# BB-OR-NAND_v1_1.net
KiCad netlist of a schematic drawn in EAGLE
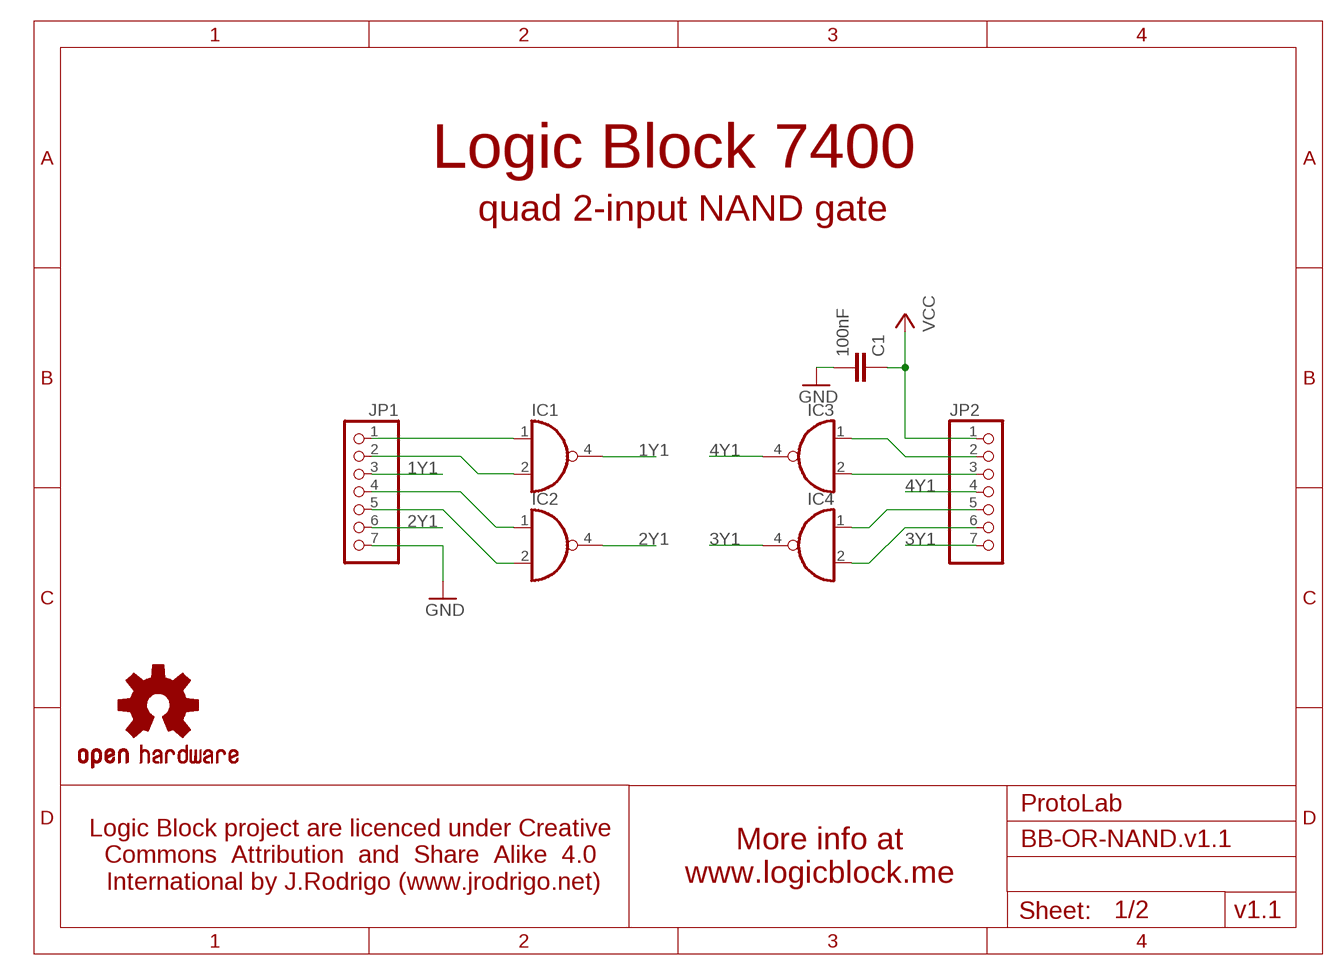
[diagram p0: schematic, sheet 1]
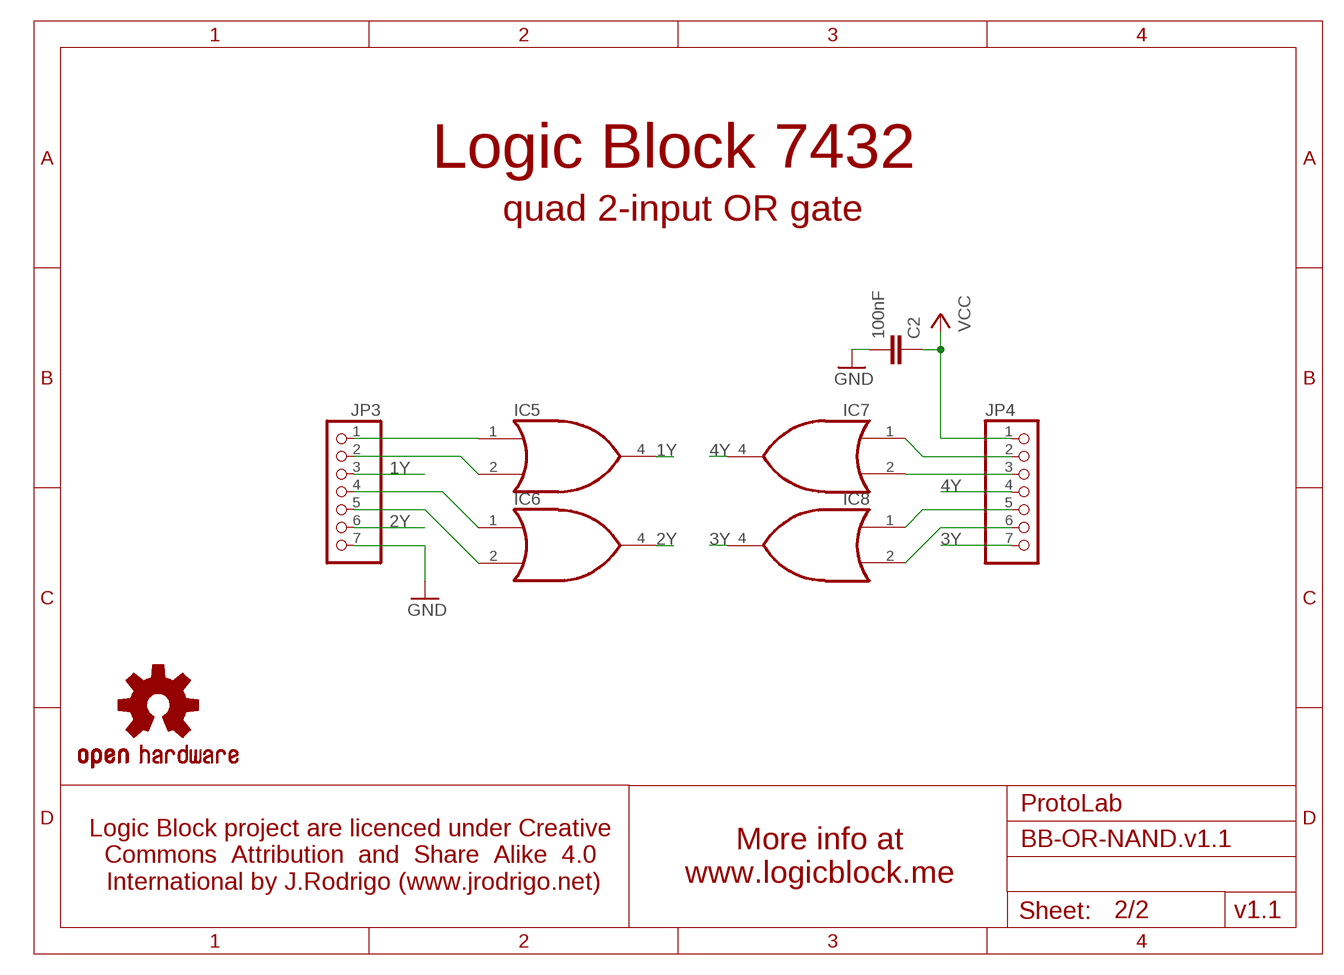
[diagram p1: schematic, sheet 2]

(export (version "E")
  (design (tool "Eeschema 10.0.6"))
  (components
    (comp (ref "C2")
      (value "100nF")
      (footprint "eagle-import:C0603K")
      (libsource (lib "eagle-import") (part "C-EUC0603K"))
    )
    (comp (ref "IC5")
      (value "74AHC1G32DCK")
      (footprint "eagle-import:SC70-5")
      (libsource (lib "eagle-import") (part "741G32DCKAHC"))
    )
    (comp (ref "IC6")
      (value "74AHC1G32DCK")
      (footprint "eagle-import:SC70-5")
      (libsource (lib "eagle-import") (part "741G32DCKAHC"))
    )
    (comp (ref "IC7")
      (value "74AHC1G32DCK")
      (footprint "eagle-import:SC70-5")
      (libsource (lib "eagle-import") (part "741G32DCKAHC"))
    )
    (comp (ref "IC8")
      (value "74AHC1G32DCK")
      (footprint "eagle-import:SC70-5")
      (libsource (lib "eagle-import") (part "741G32DCKAHC"))
    )
    (comp (ref "JP3")
      (value "CON_1X7CLEANBIG")
      (footprint "eagle-import:CON_1X07-CLEANBIG")
      (libsource (lib "eagle-import") (part "CON_1X7CLEANBIG"))
    )
    (comp (ref "JP4")
      (value "CON_1X7CLEANBIG")
      (footprint "eagle-import:CON_1X07-CLEANBIG")
      (libsource (lib "eagle-import") (part "CON_1X7CLEANBIG"))
    )
    (comp (ref "U$2")
      (value "OSHW-LOGOS-LAYER230")
      (footprint "eagle-import:OSHW-LOGO-S_LAYER230")
      (libsource (lib "eagle-import") (part "OSHW-LOGOS-LAYER230"))
    )
    (comp (ref "C1")
      (value "100nF")
      (footprint "eagle-import:C0603K")
      (libsource (lib "eagle-import") (part "C-EUC0603K"))
    )
    (comp (ref "IC1")
      (value "74AHC1G00DCK")
      (footprint "eagle-import:SC70-5")
      (libsource (lib "eagle-import") (part "741G00DCKAHC"))
    )
    (comp (ref "IC2")
      (value "74AHC1G00DCK")
      (footprint "eagle-import:SC70-5")
      (libsource (lib "eagle-import") (part "741G00DCKAHC"))
    )
    (comp (ref "IC3")
      (value "74AHC1G00DCK")
      (footprint "eagle-import:SC70-5")
      (libsource (lib "eagle-import") (part "741G00DCKAHC"))
    )
    (comp (ref "IC4")
      (value "74AHC1G00DCK")
      (footprint "eagle-import:SC70-5")
      (libsource (lib "eagle-import") (part "741G00DCKAHC"))
    )
    (comp (ref "JP1")
      (value "CON_1X7CLEANBIG")
      (footprint "eagle-import:CON_1X07-CLEANBIG")
      (libsource (lib "eagle-import") (part "CON_1X7CLEANBIG"))
    )
    (comp (ref "JP2")
      (value "CON_1X7CLEANBIG")
      (footprint "eagle-import:CON_1X07-CLEANBIG")
      (libsource (lib "eagle-import") (part "CON_1X7CLEANBIG"))
    )
    (comp (ref "U$1")
      (value "OSHW-LOGOS-LAYER230")
      (footprint "eagle-import:OSHW-LOGO-S_LAYER230")
      (libsource (lib "eagle-import") (part "OSHW-LOGOS-LAYER230"))
    )
  )
  (nets
    (net (code "1") (name "1Y") (class "Default")
      (node (ref "IC5") (pin "4") (pinfunction "O_4") (pintype "output"))
      (node (ref "JP3") (pin "3") (pinfunction "3_3") (pintype "passive"))
    )
    (net (code "2") (name "1Y1") (class "Default")
      (node (ref "IC1") (pin "4") (pinfunction "O_4") (pintype "output"))
      (node (ref "JP1") (pin "3") (pinfunction "3_3") (pintype "passive"))
    )
    (net (code "3") (name "2Y") (class "Default")
      (node (ref "IC6") (pin "4") (pinfunction "O_4") (pintype "output"))
      (node (ref "JP3") (pin "6") (pinfunction "6_6") (pintype "passive"))
    )
    (net (code "4") (name "2Y1") (class "Default")
      (node (ref "IC2") (pin "4") (pinfunction "O_4") (pintype "output"))
      (node (ref "JP1") (pin "6") (pinfunction "6_6") (pintype "passive"))
    )
    (net (code "5") (name "3Y") (class "Default")
      (node (ref "IC8") (pin "4") (pinfunction "O_4") (pintype "output"))
      (node (ref "JP4") (pin "7") (pinfunction "7_7") (pintype "passive"))
    )
    (net (code "6") (name "3Y1") (class "Default")
      (node (ref "IC4") (pin "4") (pinfunction "O_4") (pintype "output"))
      (node (ref "JP2") (pin "7") (pinfunction "7_7") (pintype "passive"))
    )
    (net (code "7") (name "4Y") (class "Default")
      (node (ref "IC7") (pin "4") (pinfunction "O_4") (pintype "output"))
      (node (ref "JP4") (pin "4") (pinfunction "4_4") (pintype "passive"))
    )
    (net (code "8") (name "4Y1") (class "Default")
      (node (ref "IC3") (pin "4") (pinfunction "O_4") (pintype "output"))
      (node (ref "JP2") (pin "4") (pinfunction "4_4") (pintype "passive"))
    )
    (net (code "9") (name "GND") (class "Default")
      (node (ref "C1") (pin "2") (pinfunction "2_2") (pintype "passive"))
      (node (ref "C2") (pin "2") (pinfunction "2_2") (pintype "passive"))
      (node (ref "JP1") (pin "7") (pinfunction "7_7") (pintype "passive"))
      (node (ref "JP3") (pin "7") (pinfunction "7_7") (pintype "passive"))
    )
    (net (code "10") (name "Net-(IC1A-I0)") (class "Default")
      (node (ref "IC1") (pin "1") (pinfunction "I0_1") (pintype "input"))
      (node (ref "JP1") (pin "1") (pinfunction "1_1") (pintype "passive"))
    )
    (net (code "11") (name "Net-(IC1A-I1)") (class "Default")
      (node (ref "IC1") (pin "2") (pinfunction "I1_2") (pintype "input"))
      (node (ref "JP1") (pin "2") (pinfunction "2_2") (pintype "passive"))
    )
    (net (code "12") (name "Net-(IC2A-I0)") (class "Default")
      (node (ref "IC2") (pin "1") (pinfunction "I0_1") (pintype "input"))
      (node (ref "JP1") (pin "4") (pinfunction "4_4") (pintype "passive"))
    )
    (net (code "13") (name "Net-(IC2A-I1)") (class "Default")
      (node (ref "IC2") (pin "2") (pinfunction "I1_2") (pintype "input"))
      (node (ref "JP1") (pin "5") (pinfunction "5_5") (pintype "passive"))
    )
    (net (code "14") (name "Net-(IC3A-I0)") (class "Default")
      (node (ref "IC3") (pin "1") (pinfunction "I0_1") (pintype "input"))
      (node (ref "JP2") (pin "2") (pinfunction "2_2") (pintype "passive"))
    )
    (net (code "15") (name "Net-(IC3A-I1)") (class "Default")
      (node (ref "IC3") (pin "2") (pinfunction "I1_2") (pintype "input"))
      (node (ref "JP2") (pin "3") (pinfunction "3_3") (pintype "passive"))
    )
    (net (code "16") (name "Net-(IC4A-I0)") (class "Default")
      (node (ref "IC4") (pin "1") (pinfunction "I0_1") (pintype "input"))
      (node (ref "JP2") (pin "5") (pinfunction "5_5") (pintype "passive"))
    )
    (net (code "17") (name "Net-(IC4A-I1)") (class "Default")
      (node (ref "IC4") (pin "2") (pinfunction "I1_2") (pintype "input"))
      (node (ref "JP2") (pin "6") (pinfunction "6_6") (pintype "passive"))
    )
    (net (code "18") (name "Net-(IC5A-I0)") (class "Default")
      (node (ref "IC5") (pin "1") (pinfunction "I0_1") (pintype "input"))
      (node (ref "JP3") (pin "1") (pinfunction "1_1") (pintype "passive"))
    )
    (net (code "19") (name "Net-(IC5A-I1)") (class "Default")
      (node (ref "IC5") (pin "2") (pinfunction "I1_2") (pintype "input"))
      (node (ref "JP3") (pin "2") (pinfunction "2_2") (pintype "passive"))
    )
    (net (code "20") (name "Net-(IC6A-I0)") (class "Default")
      (node (ref "IC6") (pin "1") (pinfunction "I0_1") (pintype "input"))
      (node (ref "JP3") (pin "4") (pinfunction "4_4") (pintype "passive"))
    )
    (net (code "21") (name "Net-(IC6A-I1)") (class "Default")
      (node (ref "IC6") (pin "2") (pinfunction "I1_2") (pintype "input"))
      (node (ref "JP3") (pin "5") (pinfunction "5_5") (pintype "passive"))
    )
    (net (code "22") (name "Net-(IC7A-I0)") (class "Default")
      (node (ref "IC7") (pin "1") (pinfunction "I0_1") (pintype "input"))
      (node (ref "JP4") (pin "2") (pinfunction "2_2") (pintype "passive"))
    )
    (net (code "23") (name "Net-(IC7A-I1)") (class "Default")
      (node (ref "IC7") (pin "2") (pinfunction "I1_2") (pintype "input"))
      (node (ref "JP4") (pin "3") (pinfunction "3_3") (pintype "passive"))
    )
    (net (code "24") (name "Net-(IC8A-I0)") (class "Default")
      (node (ref "IC8") (pin "1") (pinfunction "I0_1") (pintype "input"))
      (node (ref "JP4") (pin "5") (pinfunction "5_5") (pintype "passive"))
    )
    (net (code "25") (name "Net-(IC8A-I1)") (class "Default")
      (node (ref "IC8") (pin "2") (pinfunction "I1_2") (pintype "input"))
      (node (ref "JP4") (pin "6") (pinfunction "6_6") (pintype "passive"))
    )
    (net (code "26") (name "VCC") (class "Default")
      (node (ref "C1") (pin "1") (pinfunction "1_1") (pintype "passive"))
      (node (ref "C2") (pin "1") (pinfunction "1_1") (pintype "passive"))
      (node (ref "JP2") (pin "1") (pinfunction "1_1") (pintype "passive"))
      (node (ref "JP4") (pin "1") (pinfunction "1_1") (pintype "passive"))
    )
  )
)
